# Heart.net
KiCad netlist of a schematic drawn in Altium Designer
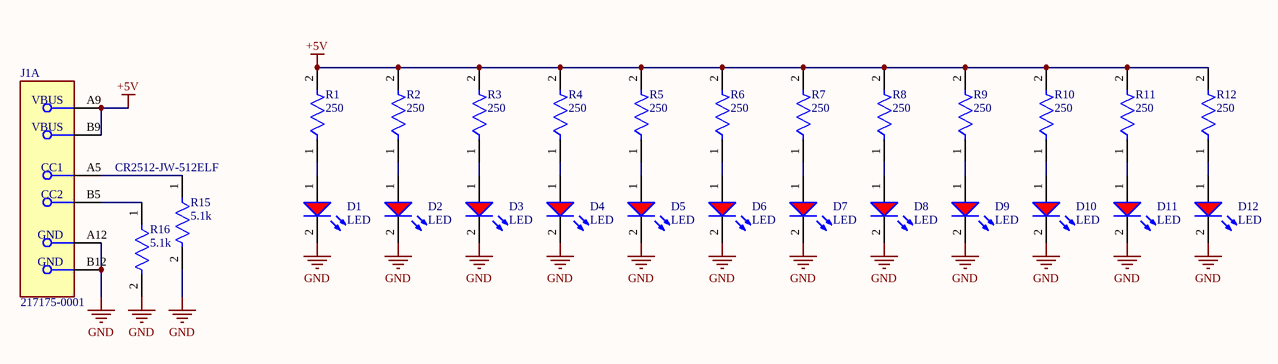
[diagram p0: Heart.SchDoc]

(export (version "E")
  (design (tool "Eeschema 10.0.6"))
  (components
    (comp (ref "D1")
      (value "LED")
      (footprint "WL-TMRC_D3.95H5.3")
      (libsource (lib "Altium Content Vault") (part "LED_Red_1A-2K"))
    )
    (comp (ref "D2")
      (value "LED")
      (footprint "WL-TMRC_D3.95H5.3")
      (libsource (lib "Altium Content Vault") (part "LED_Red_1A-2K"))
    )
    (comp (ref "D3")
      (value "LED")
      (footprint "WL-TMRC_D3.95H5.3")
      (libsource (lib "Altium Content Vault") (part "LED_Red_1A-2K"))
    )
    (comp (ref "D4")
      (value "LED")
      (footprint "WL-TMRC_D3.95H5.3")
      (libsource (lib "Altium Content Vault") (part "LED_Red_1A-2K"))
    )
    (comp (ref "D5")
      (value "LED")
      (footprint "WL-TMRC_D3.95H5.3")
      (libsource (lib "Altium Content Vault") (part "LED_Red_1A-2K"))
    )
    (comp (ref "D6")
      (value "LED")
      (footprint "WL-TMRC_D3.95H5.3")
      (libsource (lib "Altium Content Vault") (part "LED_Red_1A-2K"))
    )
    (comp (ref "D7")
      (value "LED")
      (footprint "WL-TMRC_D3.95H5.3")
      (libsource (lib "Altium Content Vault") (part "LED_Red_1A-2K"))
    )
    (comp (ref "D8")
      (value "LED")
      (footprint "WL-TMRC_D3.95H5.3")
      (libsource (lib "Altium Content Vault") (part "LED_Red_1A-2K"))
    )
    (comp (ref "D9")
      (value "LED")
      (footprint "WL-TMRC_D3.95H5.3")
      (libsource (lib "Altium Content Vault") (part "LED_Red_1A-2K"))
    )
    (comp (ref "D10")
      (value "LED")
      (footprint "WL-TMRC_D3.95H5.3")
      (libsource (lib "Altium Content Vault") (part "LED_Red_1A-2K"))
    )
    (comp (ref "D11")
      (value "LED")
      (footprint "WL-TMRC_D3.95H5.3")
      (libsource (lib "Altium Content Vault") (part "LED_Red_1A-2K"))
    )
    (comp (ref "D12")
      (value "LED")
      (footprint "WL-TMRC_D3.95H5.3")
      (libsource (lib "Altium Content Vault") (part "LED_Red_1A-2K"))
    )
    (comp (ref "J1")
      (value "217175-0001")
      (footprint "FP-217175-0001-MFG")
      (description "CONN RCP USB2.0 C 6+18P SMD RA")
      (libsource (lib "Altium Content Vault") (part "6a66c69350f09309f94811689c98437"))
    )
    (comp (ref "R1")
      (value "250")
      (footprint "FP-TFCR1206-IPC_B")
      (description "RES Thin Film, 100Ω, 0.1%, 0.125W, 25ppm/°C, 1206")
      (libsource (lib "Altium Content Vault") (part "1029c3af85768c4190bb7ad29bc67b5"))
    )
    (comp (ref "R2")
      (value "250")
      (footprint "FP-TFCR1206-IPC_B")
      (description "RES Thin Film, 100Ω, 0.1%, 0.125W, 25ppm/°C, 1206")
      (libsource (lib "Altium Content Vault") (part "1029c3af85768c4190bb7ad29bc67b5"))
    )
    (comp (ref "R3")
      (value "250")
      (footprint "FP-TFCR1206-IPC_B")
      (description "RES Thin Film, 100Ω, 0.1%, 0.125W, 25ppm/°C, 1206")
      (libsource (lib "Altium Content Vault") (part "1029c3af85768c4190bb7ad29bc67b5"))
    )
    (comp (ref "R4")
      (value "250")
      (footprint "FP-TFCR1206-IPC_B")
      (description "RES Thin Film, 100Ω, 0.1%, 0.125W, 25ppm/°C, 1206")
      (libsource (lib "Altium Content Vault") (part "1029c3af85768c4190bb7ad29bc67b5"))
    )
    (comp (ref "R5")
      (value "250")
      (footprint "FP-TFCR1206-IPC_B")
      (description "RES Thin Film, 100Ω, 0.1%, 0.125W, 25ppm/°C, 1206")
      (libsource (lib "Altium Content Vault") (part "1029c3af85768c4190bb7ad29bc67b5"))
    )
    (comp (ref "R6")
      (value "250")
      (footprint "FP-TFCR1206-IPC_B")
      (description "RES Thin Film, 100Ω, 0.1%, 0.125W, 25ppm/°C, 1206")
      (libsource (lib "Altium Content Vault") (part "1029c3af85768c4190bb7ad29bc67b5"))
    )
    (comp (ref "R7")
      (value "250")
      (footprint "FP-TFCR1206-IPC_B")
      (description "RES Thin Film, 100Ω, 0.1%, 0.125W, 25ppm/°C, 1206")
      (libsource (lib "Altium Content Vault") (part "1029c3af85768c4190bb7ad29bc67b5"))
    )
    (comp (ref "R8")
      (value "250")
      (footprint "FP-TFCR1206-IPC_B")
      (description "RES Thin Film, 100Ω, 0.1%, 0.125W, 25ppm/°C, 1206")
      (libsource (lib "Altium Content Vault") (part "1029c3af85768c4190bb7ad29bc67b5"))
    )
    (comp (ref "R9")
      (value "250")
      (footprint "FP-TFCR1206-IPC_B")
      (description "RES Thin Film, 100Ω, 0.1%, 0.125W, 25ppm/°C, 1206")
      (libsource (lib "Altium Content Vault") (part "1029c3af85768c4190bb7ad29bc67b5"))
    )
    (comp (ref "R10")
      (value "250")
      (footprint "FP-TFCR1206-IPC_B")
      (description "RES Thin Film, 100Ω, 0.1%, 0.125W, 25ppm/°C, 1206")
      (libsource (lib "Altium Content Vault") (part "1029c3af85768c4190bb7ad29bc67b5"))
    )
    (comp (ref "R11")
      (value "250")
      (footprint "FP-TFCR1206-IPC_B")
      (description "RES Thin Film, 100Ω, 0.1%, 0.125W, 25ppm/°C, 1206")
      (libsource (lib "Altium Content Vault") (part "1029c3af85768c4190bb7ad29bc67b5"))
    )
    (comp (ref "R12")
      (value "250")
      (footprint "FP-TFCR1206-IPC_B")
      (description "RES Thin Film, 100Ω, 0.1%, 0.125W, 25ppm/°C, 1206")
      (libsource (lib "Altium Content Vault") (part "1029c3af85768c4190bb7ad29bc67b5"))
    )
    (comp (ref "R15")
      (value "5.1k")
      (footprint "FP-TFCR2512-IPC_A")
      (description "RES Thin Film, 5.1kΩ, 0.5%, 0.5W, 25ppm/°C, 2512")
      (libsource (lib "Altium Content Vault") (part "1029c3af85768c4190bb7ad29bc67b5"))
    )
    (comp (ref "R16")
      (value "5.1k")
      (footprint "FP-TFCR2512-IPC_A")
      (description "RES Thin Film, 5.1kΩ, 0.5%, 0.5W, 25ppm/°C, 2512")
      (libsource (lib "Altium Content Vault") (part "1029c3af85768c4190bb7ad29bc67b5"))
    )
  )
  (nets
    (net (code "1") (name "+5V") (class "Default")
      (node (ref "J1") (pin "A9") (pinfunction "VBUS_A9") (pintype "power_in"))
      (node (ref "J1") (pin "B9") (pinfunction "VBUS_B9") (pintype "power_in"))
      (node (ref "R1") (pin "2") (pinfunction "2_2") (pintype "passive"))
      (node (ref "R10") (pin "2") (pinfunction "2_2") (pintype "passive"))
      (node (ref "R11") (pin "2") (pinfunction "2_2") (pintype "passive"))
      (node (ref "R12") (pin "2") (pinfunction "2_2") (pintype "passive"))
      (node (ref "R2") (pin "2") (pinfunction "2_2") (pintype "passive"))
      (node (ref "R3") (pin "2") (pinfunction "2_2") (pintype "passive"))
      (node (ref "R4") (pin "2") (pinfunction "2_2") (pintype "passive"))
      (node (ref "R5") (pin "2") (pinfunction "2_2") (pintype "passive"))
      (node (ref "R6") (pin "2") (pinfunction "2_2") (pintype "passive"))
      (node (ref "R7") (pin "2") (pinfunction "2_2") (pintype "passive"))
      (node (ref "R8") (pin "2") (pinfunction "2_2") (pintype "passive"))
      (node (ref "R9") (pin "2") (pinfunction "2_2") (pintype "passive"))
    )
    (net (code "2") (name "GND") (class "Default")
      (node (ref "D1") (pin "2") (pinfunction "K_2") (pintype "passive"))
      (node (ref "D10") (pin "2") (pinfunction "K_2") (pintype "passive"))
      (node (ref "D11") (pin "2") (pinfunction "K_2") (pintype "passive"))
      (node (ref "D12") (pin "2") (pinfunction "K_2") (pintype "passive"))
      (node (ref "D2") (pin "2") (pinfunction "K_2") (pintype "passive"))
      (node (ref "D3") (pin "2") (pinfunction "K_2") (pintype "passive"))
      (node (ref "D4") (pin "2") (pinfunction "K_2") (pintype "passive"))
      (node (ref "D5") (pin "2") (pinfunction "K_2") (pintype "passive"))
      (node (ref "D6") (pin "2") (pinfunction "K_2") (pintype "passive"))
      (node (ref "D7") (pin "2") (pinfunction "K_2") (pintype "passive"))
      (node (ref "D8") (pin "2") (pinfunction "K_2") (pintype "passive"))
      (node (ref "D9") (pin "2") (pinfunction "K_2") (pintype "passive"))
      (node (ref "J1") (pin "A12") (pinfunction "GND_A12") (pintype "power_in"))
      (node (ref "J1") (pin "B12") (pinfunction "GND_B12") (pintype "power_in"))
      (node (ref "R15") (pin "2") (pinfunction "2_2") (pintype "passive"))
      (node (ref "R16") (pin "2") (pinfunction "2_2") (pintype "passive"))
    )
    (net (code "3") (name "Net-(D1-A)") (class "Default")
      (node (ref "D1") (pin "1") (pinfunction "A_1") (pintype "passive"))
      (node (ref "R1") (pin "1") (pinfunction "1_1") (pintype "passive"))
    )
    (net (code "4") (name "Net-(D2-A)") (class "Default")
      (node (ref "D2") (pin "1") (pinfunction "A_1") (pintype "passive"))
      (node (ref "R2") (pin "1") (pinfunction "1_1") (pintype "passive"))
    )
    (net (code "5") (name "Net-(D3-A)") (class "Default")
      (node (ref "D3") (pin "1") (pinfunction "A_1") (pintype "passive"))
      (node (ref "R3") (pin "1") (pinfunction "1_1") (pintype "passive"))
    )
    (net (code "6") (name "Net-(D4-A)") (class "Default")
      (node (ref "D4") (pin "1") (pinfunction "A_1") (pintype "passive"))
      (node (ref "R4") (pin "1") (pinfunction "1_1") (pintype "passive"))
    )
    (net (code "7") (name "Net-(D5-A)") (class "Default")
      (node (ref "D5") (pin "1") (pinfunction "A_1") (pintype "passive"))
      (node (ref "R5") (pin "1") (pinfunction "1_1") (pintype "passive"))
    )
    (net (code "8") (name "Net-(D6-A)") (class "Default")
      (node (ref "D6") (pin "1") (pinfunction "A_1") (pintype "passive"))
      (node (ref "R6") (pin "1") (pinfunction "1_1") (pintype "passive"))
    )
    (net (code "9") (name "Net-(D7-A)") (class "Default")
      (node (ref "D7") (pin "1") (pinfunction "A_1") (pintype "passive"))
      (node (ref "R7") (pin "1") (pinfunction "1_1") (pintype "passive"))
    )
    (net (code "10") (name "Net-(D8-A)") (class "Default")
      (node (ref "D8") (pin "1") (pinfunction "A_1") (pintype "passive"))
      (node (ref "R8") (pin "1") (pinfunction "1_1") (pintype "passive"))
    )
    (net (code "11") (name "Net-(D9-A)") (class "Default")
      (node (ref "D9") (pin "1") (pinfunction "A_1") (pintype "passive"))
      (node (ref "R9") (pin "1") (pinfunction "1_1") (pintype "passive"))
    )
    (net (code "12") (name "Net-(D10-A)") (class "Default")
      (node (ref "D10") (pin "1") (pinfunction "A_1") (pintype "passive"))
      (node (ref "R10") (pin "1") (pinfunction "1_1") (pintype "passive"))
    )
    (net (code "13") (name "Net-(D11-A)") (class "Default")
      (node (ref "D11") (pin "1") (pinfunction "A_1") (pintype "passive"))
      (node (ref "R11") (pin "1") (pinfunction "1_1") (pintype "passive"))
    )
    (net (code "14") (name "Net-(D12-A)") (class "Default")
      (node (ref "D12") (pin "1") (pinfunction "A_1") (pintype "passive"))
      (node (ref "R12") (pin "1") (pinfunction "1_1") (pintype "passive"))
    )
    (net (code "15") (name "Net-(J1A-CC1)") (class "Default")
      (node (ref "J1") (pin "A5") (pinfunction "CC1_A5") (pintype "passive"))
      (node (ref "R15") (pin "1") (pinfunction "1_1") (pintype "passive"))
    )
    (net (code "16") (name "Net-(J1A-CC2)") (class "Default")
      (node (ref "J1") (pin "B5") (pinfunction "CC2_B5") (pintype "passive"))
      (node (ref "R16") (pin "1") (pinfunction "1_1") (pintype "passive"))
    )
  )
)
